# PIUDaughterBoardV2.net
KiCad netlist of a schematic drawn in EAGLE
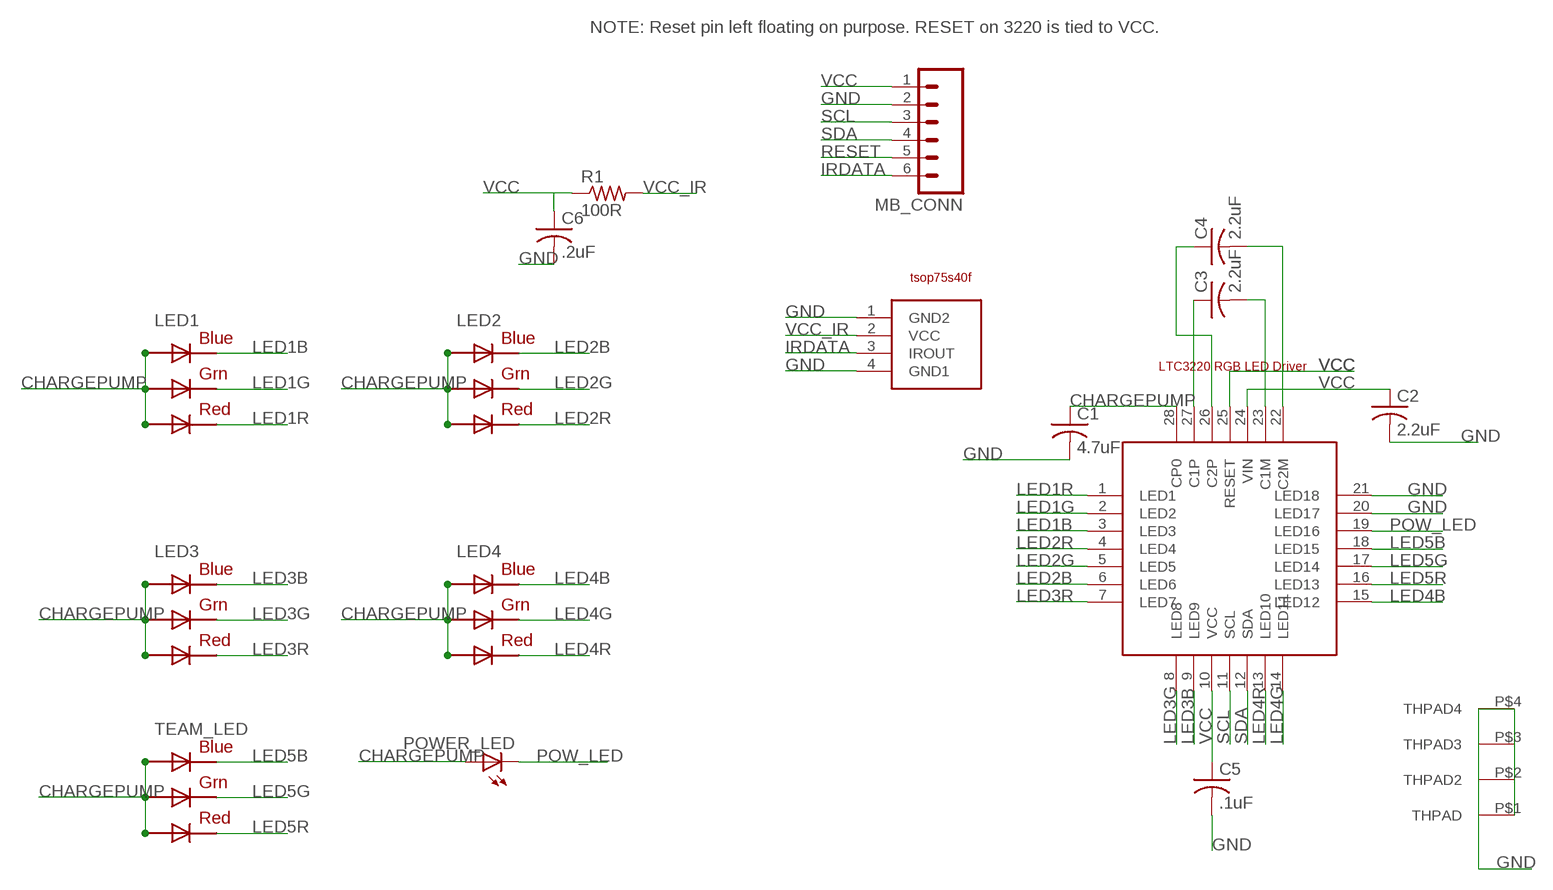
[diagram p0: schematic, sheet 1]

(export (version "E")
  (design (tool "Eeschema 10.0.6"))
  (components
    (comp (ref "C1")
      (value "4.7uF")
      (footprint "eagle-import:C0603")
      (libsource (lib "eagle-import") (part "C-USC0603"))
    )
    (comp (ref "C2")
      (value "2.2uF")
      (footprint "eagle-import:C0603")
      (libsource (lib "eagle-import") (part "C-USC0603"))
    )
    (comp (ref "C3")
      (value "2.2uF")
      (footprint "eagle-import:C0603")
      (libsource (lib "eagle-import") (part "C-USC0603"))
    )
    (comp (ref "C4")
      (value "2.2uF")
      (footprint "eagle-import:C0603")
      (libsource (lib "eagle-import") (part "C-USC0603"))
    )
    (comp (ref "C5")
      (value ".1uF")
      (footprint "eagle-import:C0603")
      (libsource (lib "eagle-import") (part "C-USC0603"))
    )
    (comp (ref "C6")
      (value ".2uF")
      (footprint "eagle-import:C0603")
      (libsource (lib "eagle-import") (part "C-USC0603"))
    )
    (comp (ref "LED1")
      (value "RGBLED5050")
      (footprint "eagle-import:RGBLED5050")
      (libsource (lib "eagle-import") (part "RGBLED5050"))
    )
    (comp (ref "LED2")
      (value "RGBLED5050")
      (footprint "eagle-import:RGBLED5050")
      (libsource (lib "eagle-import") (part "RGBLED5050"))
    )
    (comp (ref "LED3")
      (value "RGBLED5050")
      (footprint "eagle-import:RGBLED5050")
      (libsource (lib "eagle-import") (part "RGBLED5050"))
    )
    (comp (ref "LED4")
      (value "RGBLED5050")
      (footprint "eagle-import:RGBLED5050")
      (libsource (lib "eagle-import") (part "RGBLED5050"))
    )
    (comp (ref "MB_CONN")
      (value "M06SMD_MALE")
      (footprint "eagle-import:1X06_SMD_MALE")
      (libsource (lib "eagle-import") (part "M06SMD_MALE"))
    )
    (comp (ref "POWER_LED")
      (value "LEDCHIPLED_0805")
      (footprint "eagle-import:CHIPLED_0805")
      (libsource (lib "eagle-import") (part "LEDCHIPLED_0805"))
    )
    (comp (ref "R1")
      (value "100R")
      (footprint "eagle-import:R0603")
      (libsource (lib "eagle-import") (part "R-US_R0603"))
    )
    (comp (ref "TEAM_LED")
      (value "RGBLED5050")
      (footprint "eagle-import:RGBLED5050")
      (libsource (lib "eagle-import") (part "RGBLED5050"))
    )
    (comp (ref "U$1")
      (value "TSOP75S40F")
      (footprint "eagle-import:TSOP75S40F")
      (libsource (lib "eagle-import") (part "TSOP75S40F"))
    )
    (comp (ref "U$3")
      (value "LTC3220")
      (footprint "eagle-import:LTC3220")
      (libsource (lib "eagle-import") (part "LTC3220"))
    )
  )
  (nets
    (net (code "1") (name "/CHARGEPUMP") (class "Default")
      (node (ref "C1") (pin "1") (pinfunction "1_1") (pintype "passive"))
      (node (ref "LED1") (pin "1") (pinfunction "GREEN_A_1") (pintype "bidirectional"))
      (node (ref "LED1") (pin "2") (pinfunction "RED_A_2") (pintype "bidirectional"))
      (node (ref "LED1") (pin "3") (pinfunction "BLUE_A_3") (pintype "bidirectional"))
      (node (ref "LED2") (pin "1") (pinfunction "GREEN_A_1") (pintype "bidirectional"))
      (node (ref "LED2") (pin "2") (pinfunction "RED_A_2") (pintype "bidirectional"))
      (node (ref "LED2") (pin "3") (pinfunction "BLUE_A_3") (pintype "bidirectional"))
      (node (ref "LED3") (pin "1") (pinfunction "GREEN_A_1") (pintype "bidirectional"))
      (node (ref "LED3") (pin "2") (pinfunction "RED_A_2") (pintype "bidirectional"))
      (node (ref "LED3") (pin "3") (pinfunction "BLUE_A_3") (pintype "bidirectional"))
      (node (ref "LED4") (pin "1") (pinfunction "GREEN_A_1") (pintype "bidirectional"))
      (node (ref "LED4") (pin "2") (pinfunction "RED_A_2") (pintype "bidirectional"))
      (node (ref "LED4") (pin "3") (pinfunction "BLUE_A_3") (pintype "bidirectional"))
      (node (ref "POWER_LED") (pin "A") (pinfunction "A_A") (pintype "passive"))
      (node (ref "TEAM_LED") (pin "1") (pinfunction "GREEN_A_1") (pintype "bidirectional"))
      (node (ref "TEAM_LED") (pin "2") (pinfunction "RED_A_2") (pintype "bidirectional"))
      (node (ref "TEAM_LED") (pin "3") (pinfunction "BLUE_A_3") (pintype "bidirectional"))
      (node (ref "U$3") (pin "28") (pinfunction "CP0_28") (pintype "bidirectional"))
    )
    (net (code "2") (name "/GND") (class "Default")
      (node (ref "C1") (pin "2") (pinfunction "2_2") (pintype "passive"))
      (node (ref "C2") (pin "2") (pinfunction "2_2") (pintype "passive"))
      (node (ref "C5") (pin "2") (pinfunction "2_2") (pintype "passive"))
      (node (ref "C6") (pin "2") (pinfunction "2_2") (pintype "passive"))
      (node (ref "MB_CONN") (pin "2") (pinfunction "2_2") (pintype "passive"))
      (node (ref "U$1") (pin "1") (pinfunction "GND2_1") (pintype "bidirectional"))
      (node (ref "U$1") (pin "4") (pinfunction "GND1_4") (pintype "bidirectional"))
      (node (ref "U$3") (pin "20") (pinfunction "LED17_20") (pintype "bidirectional"))
      (node (ref "U$3") (pin "21") (pinfunction "LED18_21") (pintype "bidirectional"))
      (node (ref "U$3") (pin "P$1") (pinfunction "THPAD_P$1") (pintype "bidirectional"))
      (node (ref "U$3") (pin "P$2") (pinfunction "THPAD2_P$2") (pintype "bidirectional"))
      (node (ref "U$3") (pin "P$3") (pinfunction "THPAD3_P$3") (pintype "bidirectional"))
      (node (ref "U$3") (pin "P$4") (pinfunction "THPAD4_P$4") (pintype "bidirectional"))
    )
    (net (code "3") (name "/IRDATA") (class "Default")
      (node (ref "MB_CONN") (pin "6") (pinfunction "6_6") (pintype "passive"))
      (node (ref "U$1") (pin "3") (pinfunction "IROUT_3") (pintype "bidirectional"))
    )
    (net (code "4") (name "/LED1B") (class "Default")
      (node (ref "LED1") (pin "4") (pinfunction "BLUE_C_4") (pintype "bidirectional"))
      (node (ref "U$3") (pin "3") (pinfunction "LED3_3") (pintype "bidirectional"))
    )
    (net (code "5") (name "/LED1G") (class "Default")
      (node (ref "LED1") (pin "6") (pinfunction "GREEN_C_6") (pintype "bidirectional"))
      (node (ref "U$3") (pin "2") (pinfunction "LED2_2") (pintype "bidirectional"))
    )
    (net (code "6") (name "/LED1R") (class "Default")
      (node (ref "LED1") (pin "5") (pinfunction "RED_C_5") (pintype "bidirectional"))
      (node (ref "U$3") (pin "1") (pinfunction "LED1_1") (pintype "bidirectional"))
    )
    (net (code "7") (name "/LED2B") (class "Default")
      (node (ref "LED2") (pin "4") (pinfunction "BLUE_C_4") (pintype "bidirectional"))
      (node (ref "U$3") (pin "6") (pinfunction "LED6_6") (pintype "bidirectional"))
    )
    (net (code "8") (name "/LED2G") (class "Default")
      (node (ref "LED2") (pin "6") (pinfunction "GREEN_C_6") (pintype "bidirectional"))
      (node (ref "U$3") (pin "5") (pinfunction "LED5_5") (pintype "bidirectional"))
    )
    (net (code "9") (name "/LED2R") (class "Default")
      (node (ref "LED2") (pin "5") (pinfunction "RED_C_5") (pintype "bidirectional"))
      (node (ref "U$3") (pin "4") (pinfunction "LED4_4") (pintype "bidirectional"))
    )
    (net (code "10") (name "/LED3B") (class "Default")
      (node (ref "LED3") (pin "4") (pinfunction "BLUE_C_4") (pintype "bidirectional"))
      (node (ref "U$3") (pin "9") (pinfunction "LED9_9") (pintype "bidirectional"))
    )
    (net (code "11") (name "/LED3G") (class "Default")
      (node (ref "LED3") (pin "6") (pinfunction "GREEN_C_6") (pintype "bidirectional"))
      (node (ref "U$3") (pin "8") (pinfunction "LED8_8") (pintype "bidirectional"))
    )
    (net (code "12") (name "/LED3R") (class "Default")
      (node (ref "LED3") (pin "5") (pinfunction "RED_C_5") (pintype "bidirectional"))
      (node (ref "U$3") (pin "7") (pinfunction "LED7_7") (pintype "bidirectional"))
    )
    (net (code "13") (name "/LED4B") (class "Default")
      (node (ref "LED4") (pin "4") (pinfunction "BLUE_C_4") (pintype "bidirectional"))
      (node (ref "U$3") (pin "15") (pinfunction "LED12_15") (pintype "bidirectional"))
    )
    (net (code "14") (name "/LED4G") (class "Default")
      (node (ref "LED4") (pin "6") (pinfunction "GREEN_C_6") (pintype "bidirectional"))
      (node (ref "U$3") (pin "14") (pinfunction "LED11_14") (pintype "bidirectional"))
    )
    (net (code "15") (name "/LED4R") (class "Default")
      (node (ref "LED4") (pin "5") (pinfunction "RED_C_5") (pintype "bidirectional"))
      (node (ref "U$3") (pin "13") (pinfunction "LED10_13") (pintype "bidirectional"))
    )
    (net (code "16") (name "/LED5B") (class "Default")
      (node (ref "TEAM_LED") (pin "4") (pinfunction "BLUE_C_4") (pintype "bidirectional"))
      (node (ref "U$3") (pin "18") (pinfunction "LED15_18") (pintype "bidirectional"))
    )
    (net (code "17") (name "/LED5G") (class "Default")
      (node (ref "TEAM_LED") (pin "6") (pinfunction "GREEN_C_6") (pintype "bidirectional"))
      (node (ref "U$3") (pin "17") (pinfunction "LED14_17") (pintype "bidirectional"))
    )
    (net (code "18") (name "/LED5R") (class "Default")
      (node (ref "TEAM_LED") (pin "5") (pinfunction "RED_C_5") (pintype "bidirectional"))
      (node (ref "U$3") (pin "16") (pinfunction "LED13_16") (pintype "bidirectional"))
    )
    (net (code "19") (name "/POW_LED") (class "Default")
      (node (ref "POWER_LED") (pin "C") (pinfunction "C_C") (pintype "passive"))
      (node (ref "U$3") (pin "19") (pinfunction "LED16_19") (pintype "bidirectional"))
    )
    (net (code "20") (name "/RESET") (class "Default")
      (node (ref "MB_CONN") (pin "5") (pinfunction "5_5") (pintype "passive"))
    )
    (net (code "21") (name "/SCL") (class "Default")
      (node (ref "MB_CONN") (pin "3") (pinfunction "3_3") (pintype "passive"))
      (node (ref "U$3") (pin "11") (pinfunction "SCL_11") (pintype "bidirectional"))
    )
    (net (code "22") (name "/SDA") (class "Default")
      (node (ref "MB_CONN") (pin "4") (pinfunction "4_4") (pintype "passive"))
      (node (ref "U$3") (pin "12") (pinfunction "SDA_12") (pintype "bidirectional"))
    )
    (net (code "23") (name "/VCC") (class "Default")
      (node (ref "C2") (pin "1") (pinfunction "1_1") (pintype "passive"))
      (node (ref "C5") (pin "1") (pinfunction "1_1") (pintype "passive"))
      (node (ref "C6") (pin "1") (pinfunction "1_1") (pintype "passive"))
      (node (ref "MB_CONN") (pin "1") (pinfunction "1_1") (pintype "passive"))
      (node (ref "R1") (pin "1") (pinfunction "1_1") (pintype "passive"))
      (node (ref "U$3") (pin "10") (pinfunction "VCC_10") (pintype "bidirectional"))
      (node (ref "U$3") (pin "24") (pinfunction "VIN_24") (pintype "bidirectional"))
      (node (ref "U$3") (pin "25") (pinfunction "RESET_25") (pintype "bidirectional"))
    )
    (net (code "24") (name "/VCC_IR") (class "Default")
      (node (ref "R1") (pin "2") (pinfunction "2_2") (pintype "passive"))
      (node (ref "U$1") (pin "2") (pinfunction "VCC_2") (pintype "bidirectional"))
    )
    (net (code "25") (name "Net-(U$3-C1M)") (class "Default")
      (node (ref "C3") (pin "2") (pinfunction "2_2") (pintype "passive"))
      (node (ref "U$3") (pin "23") (pinfunction "C1M_23") (pintype "bidirectional"))
    )
    (net (code "26") (name "Net-(U$3-C1P)") (class "Default")
      (node (ref "C3") (pin "1") (pinfunction "1_1") (pintype "passive"))
      (node (ref "U$3") (pin "27") (pinfunction "C1P_27") (pintype "bidirectional"))
    )
    (net (code "27") (name "Net-(U$3-C2M)") (class "Default")
      (node (ref "C4") (pin "2") (pinfunction "2_2") (pintype "passive"))
      (node (ref "U$3") (pin "22") (pinfunction "C2M_22") (pintype "bidirectional"))
    )
    (net (code "28") (name "Net-(U$3-C2P)") (class "Default")
      (node (ref "C4") (pin "1") (pinfunction "1_1") (pintype "passive"))
      (node (ref "U$3") (pin "26") (pinfunction "C2P_26") (pintype "bidirectional"))
    )
  )
)
